# Power_Management.net
KiCad netlist of a schematic drawn in Altium Designer
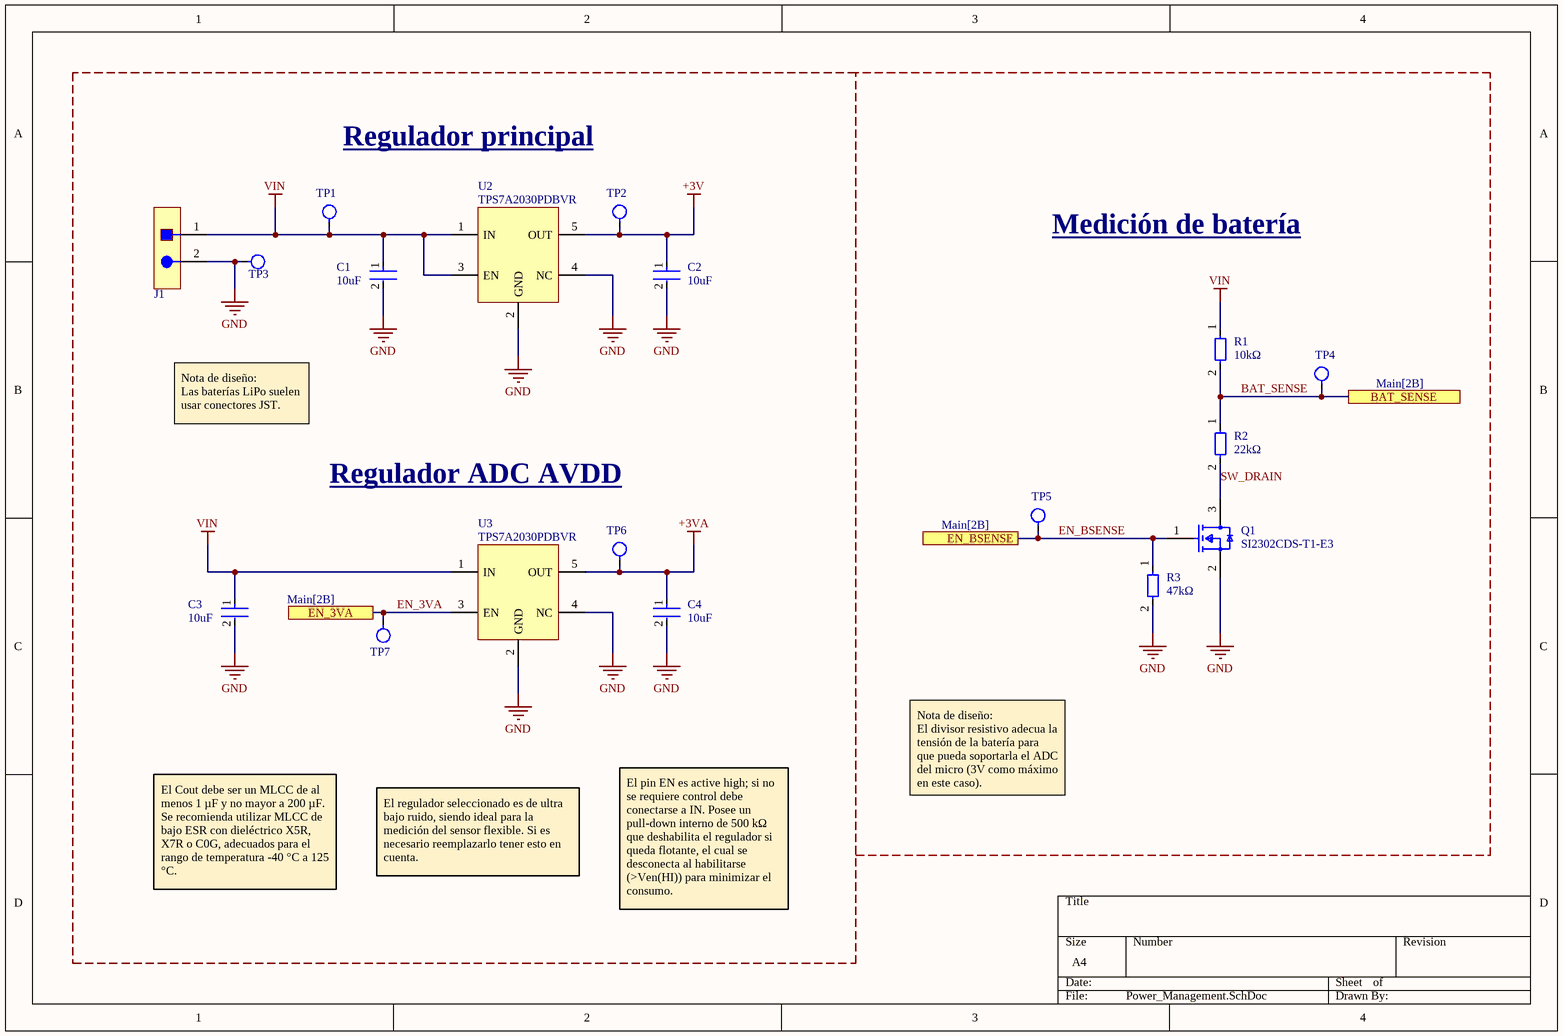
[diagram p0: Power_Management.SchDoc]

(export (version "E")
  (design (tool "Eeschema 10.0.6"))
  (components
    (comp (ref "C1")
      (value "10uF")
      (footprint "CAP_0603")
      (description "Cap 10 uF 10V X7R 0603")
      (fields (field (name "CAPACITANCE") "10uF") (field (name "TOLERANCE") "10%"))
      (libsource (lib "Passive_Components") (part "Generic C"))
    )
    (comp (ref "C2")
      (value "10uF")
      (footprint "CAP_0603")
      (description "Cap 10 uF 10V X7R 0603")
      (fields (field (name "CAPACITANCE") "10uF") (field (name "TOLERANCE") "10%"))
      (libsource (lib "Passive_Components") (part "Generic C"))
    )
    (comp (ref "C3")
      (value "10uF")
      (footprint "CAP_0603")
      (description "Cap 10 uF 10V X7R 0603")
      (fields (field (name "CAPACITANCE") "10uF") (field (name "TOLERANCE") "10%"))
      (libsource (lib "Passive_Components") (part "Generic C"))
    )
    (comp (ref "C4")
      (value "10uF")
      (footprint "CAP_0603")
      (description "Cap 10 uF 10V X7R 0603")
      (fields (field (name "CAPACITANCE") "10uF") (field (name "TOLERANCE") "10%"))
      (libsource (lib "Passive_Components") (part "Generic C"))
    )
    (comp (ref "J1")
      (value "JST CONN")
      (footprint "JST_B2B-PH-K-S")
      (description "CONN JST HEADER VERT 2POS 2MM for LIPO batteries.")
      (libsource (lib "Connectors") (part "B2B-PH-K-S"))
    )
    (comp (ref "Q1")
      (value "SI2302CDS-T1-E3")
      (footprint "FP-S-03946-MFG")
      (description "MOSFET N-CH 20V 2.6A SOT-23")
      (fields
        (field (name "MANUFACTURER") "Vishay")
        (field (name "OCTOPART") "https://octopart.com/si2302cds-t1-e3-vishay-44452855")
      )
      (libsource (lib "Altium Content Vault") (part "3b9c635fedb024a5347a57b145af9cc"))
    )
    (comp (ref "R1")
      (value "10kΩ")
      (footprint "RES_0603")
      (description "RES  10k 1% 0603")
      (fields (field (name "Comment") "10k"))
      (libsource (lib "Passive_Components") (part "Generic R"))
    )
    (comp (ref "R2")
      (value "22kΩ")
      (footprint "RES_0603")
      (description "RES  22k 1% 0603")
      (fields (field (name "Comment") "22k"))
      (libsource (lib "Passive_Components") (part "Generic R"))
    )
    (comp (ref "R3")
      (value "47kΩ")
      (footprint "RES_0603")
      (description "RES  47k 1% 0603")
      (fields (field (name "Comment") "47k"))
      (libsource (lib "Passive_Components") (part "Generic R"))
    )
    (comp (ref "TP1")
      (value "Testpoint SMD")
      (footprint "Testpoint_SMD")
      (description "Testpoint SMD de 1mm de diametro.")
      (libsource (lib "Connectors") (part "Testpoint_SMD"))
    )
    (comp (ref "TP2")
      (value "Testpoint SMD")
      (footprint "Testpoint_SMD")
      (description "Testpoint SMD de 1mm de diametro.")
      (libsource (lib "Connectors") (part "Testpoint_SMD"))
    )
    (comp (ref "TP3")
      (value "Testpoint SMD")
      (footprint "Testpoint_SMD")
      (description "Testpoint SMD de 1mm de diametro.")
      (libsource (lib "Connectors") (part "Testpoint_SMD"))
    )
    (comp (ref "TP4")
      (value "Testpoint SMD")
      (footprint "Testpoint_SMD")
      (description "Testpoint SMD de 1mm de diametro.")
      (libsource (lib "Connectors") (part "Testpoint_SMD"))
    )
    (comp (ref "TP5")
      (value "Testpoint SMD")
      (footprint "Testpoint_SMD")
      (description "Testpoint SMD de 1mm de diametro.")
      (libsource (lib "Connectors") (part "Testpoint_SMD"))
    )
    (comp (ref "TP6")
      (value "Testpoint SMD")
      (footprint "Testpoint_SMD")
      (description "Testpoint SMD de 1mm de diametro.")
      (libsource (lib "Connectors") (part "Testpoint_SMD"))
    )
    (comp (ref "TP7")
      (value "Testpoint SMD")
      (footprint "Testpoint_SMD")
      (description "Testpoint SMD de 1mm de diametro.")
      (libsource (lib "Connectors") (part "Testpoint_SMD"))
    )
    (comp (ref "U2")
      (value "TPS7A2030PDBVR")
      (footprint "SOT-23")
      (description "IC REG LINEAR 3V 300MA SOT23-5")
      (libsource (lib "Power_Management") (part "TPS7A2030PDBVR"))
    )
    (comp (ref "U3")
      (value "TPS7A2030PDBVR")
      (footprint "SOT-23")
      (description "IC REG LINEAR 3V 300MA SOT23-5")
      (libsource (lib "Power_Management") (part "TPS7A2030PDBVR"))
    )
  )
  (nets
    (net (code "1") (name "+3V") (class "Default")
      (node (ref "C2") (pin "1") (pinfunction "1_1") (pintype "passive"))
      (node (ref "TP2") (pin "1") (pinfunction "1_1") (pintype "passive"))
      (node (ref "U2") (pin "5") (pinfunction "OUT_5") (pintype "passive"))
    )
    (net (code "2") (name "+3VA") (class "Default")
      (node (ref "C4") (pin "1") (pinfunction "1_1") (pintype "passive"))
      (node (ref "TP6") (pin "1") (pinfunction "1_1") (pintype "passive"))
      (node (ref "U3") (pin "5") (pinfunction "OUT_5") (pintype "passive"))
    )
    (net (code "3") (name "/BAT_SENSE") (class "Default")
      (node (ref "R1") (pin "2") (pinfunction "2_2") (pintype "passive"))
      (node (ref "R2") (pin "1") (pinfunction "1_1") (pintype "passive"))
      (node (ref "TP4") (pin "1") (pinfunction "1_1") (pintype "passive"))
    )
    (net (code "4") (name "/EN_3VA") (class "Default")
      (node (ref "TP7") (pin "1") (pinfunction "1_1") (pintype "passive"))
      (node (ref "U3") (pin "3") (pinfunction "EN_3") (pintype "passive"))
    )
    (net (code "5") (name "/EN_BSENSE") (class "Default")
      (node (ref "Q1") (pin "1") (pinfunction "G_1") (pintype "passive"))
      (node (ref "R3") (pin "1") (pinfunction "1_1") (pintype "passive"))
      (node (ref "TP5") (pin "1") (pinfunction "1_1") (pintype "passive"))
    )
    (net (code "6") (name "/SW_DRAIN") (class "Default")
      (node (ref "Q1") (pin "3") (pinfunction "D_3") (pintype "passive"))
      (node (ref "R2") (pin "2") (pinfunction "2_2") (pintype "passive"))
    )
    (net (code "7") (name "GND") (class "Default")
      (node (ref "C1") (pin "2") (pinfunction "2_2") (pintype "passive"))
      (node (ref "C2") (pin "2") (pinfunction "2_2") (pintype "passive"))
      (node (ref "C3") (pin "2") (pinfunction "2_2") (pintype "passive"))
      (node (ref "C4") (pin "2") (pinfunction "2_2") (pintype "passive"))
      (node (ref "J1") (pin "2") (pinfunction "2_2") (pintype "passive"))
      (node (ref "Q1") (pin "2") (pinfunction "S_2") (pintype "passive"))
      (node (ref "R3") (pin "2") (pinfunction "2_2") (pintype "passive"))
      (node (ref "TP3") (pin "1") (pinfunction "1_1") (pintype "passive"))
      (node (ref "U2") (pin "2") (pinfunction "GND_2") (pintype "passive"))
      (node (ref "U2") (pin "4") (pinfunction "NC_4") (pintype "passive"))
      (node (ref "U3") (pin "2") (pinfunction "GND_2") (pintype "passive"))
      (node (ref "U3") (pin "4") (pinfunction "NC_4") (pintype "passive"))
    )
    (net (code "8") (name "VIN") (class "Default")
      (node (ref "C1") (pin "1") (pinfunction "1_1") (pintype "passive"))
      (node (ref "C3") (pin "1") (pinfunction "1_1") (pintype "passive"))
      (node (ref "J1") (pin "1") (pinfunction "1_1") (pintype "passive"))
      (node (ref "R1") (pin "1") (pinfunction "1_1") (pintype "passive"))
      (node (ref "TP1") (pin "1") (pinfunction "1_1") (pintype "passive"))
      (node (ref "U2") (pin "1") (pinfunction "IN_1") (pintype "passive"))
      (node (ref "U2") (pin "3") (pinfunction "EN_3") (pintype "passive"))
      (node (ref "U3") (pin "1") (pinfunction "IN_1") (pintype "passive"))
    )
  )
)
